# S5_Communications.net
KiCad netlist of a schematic drawn in Altium Designer
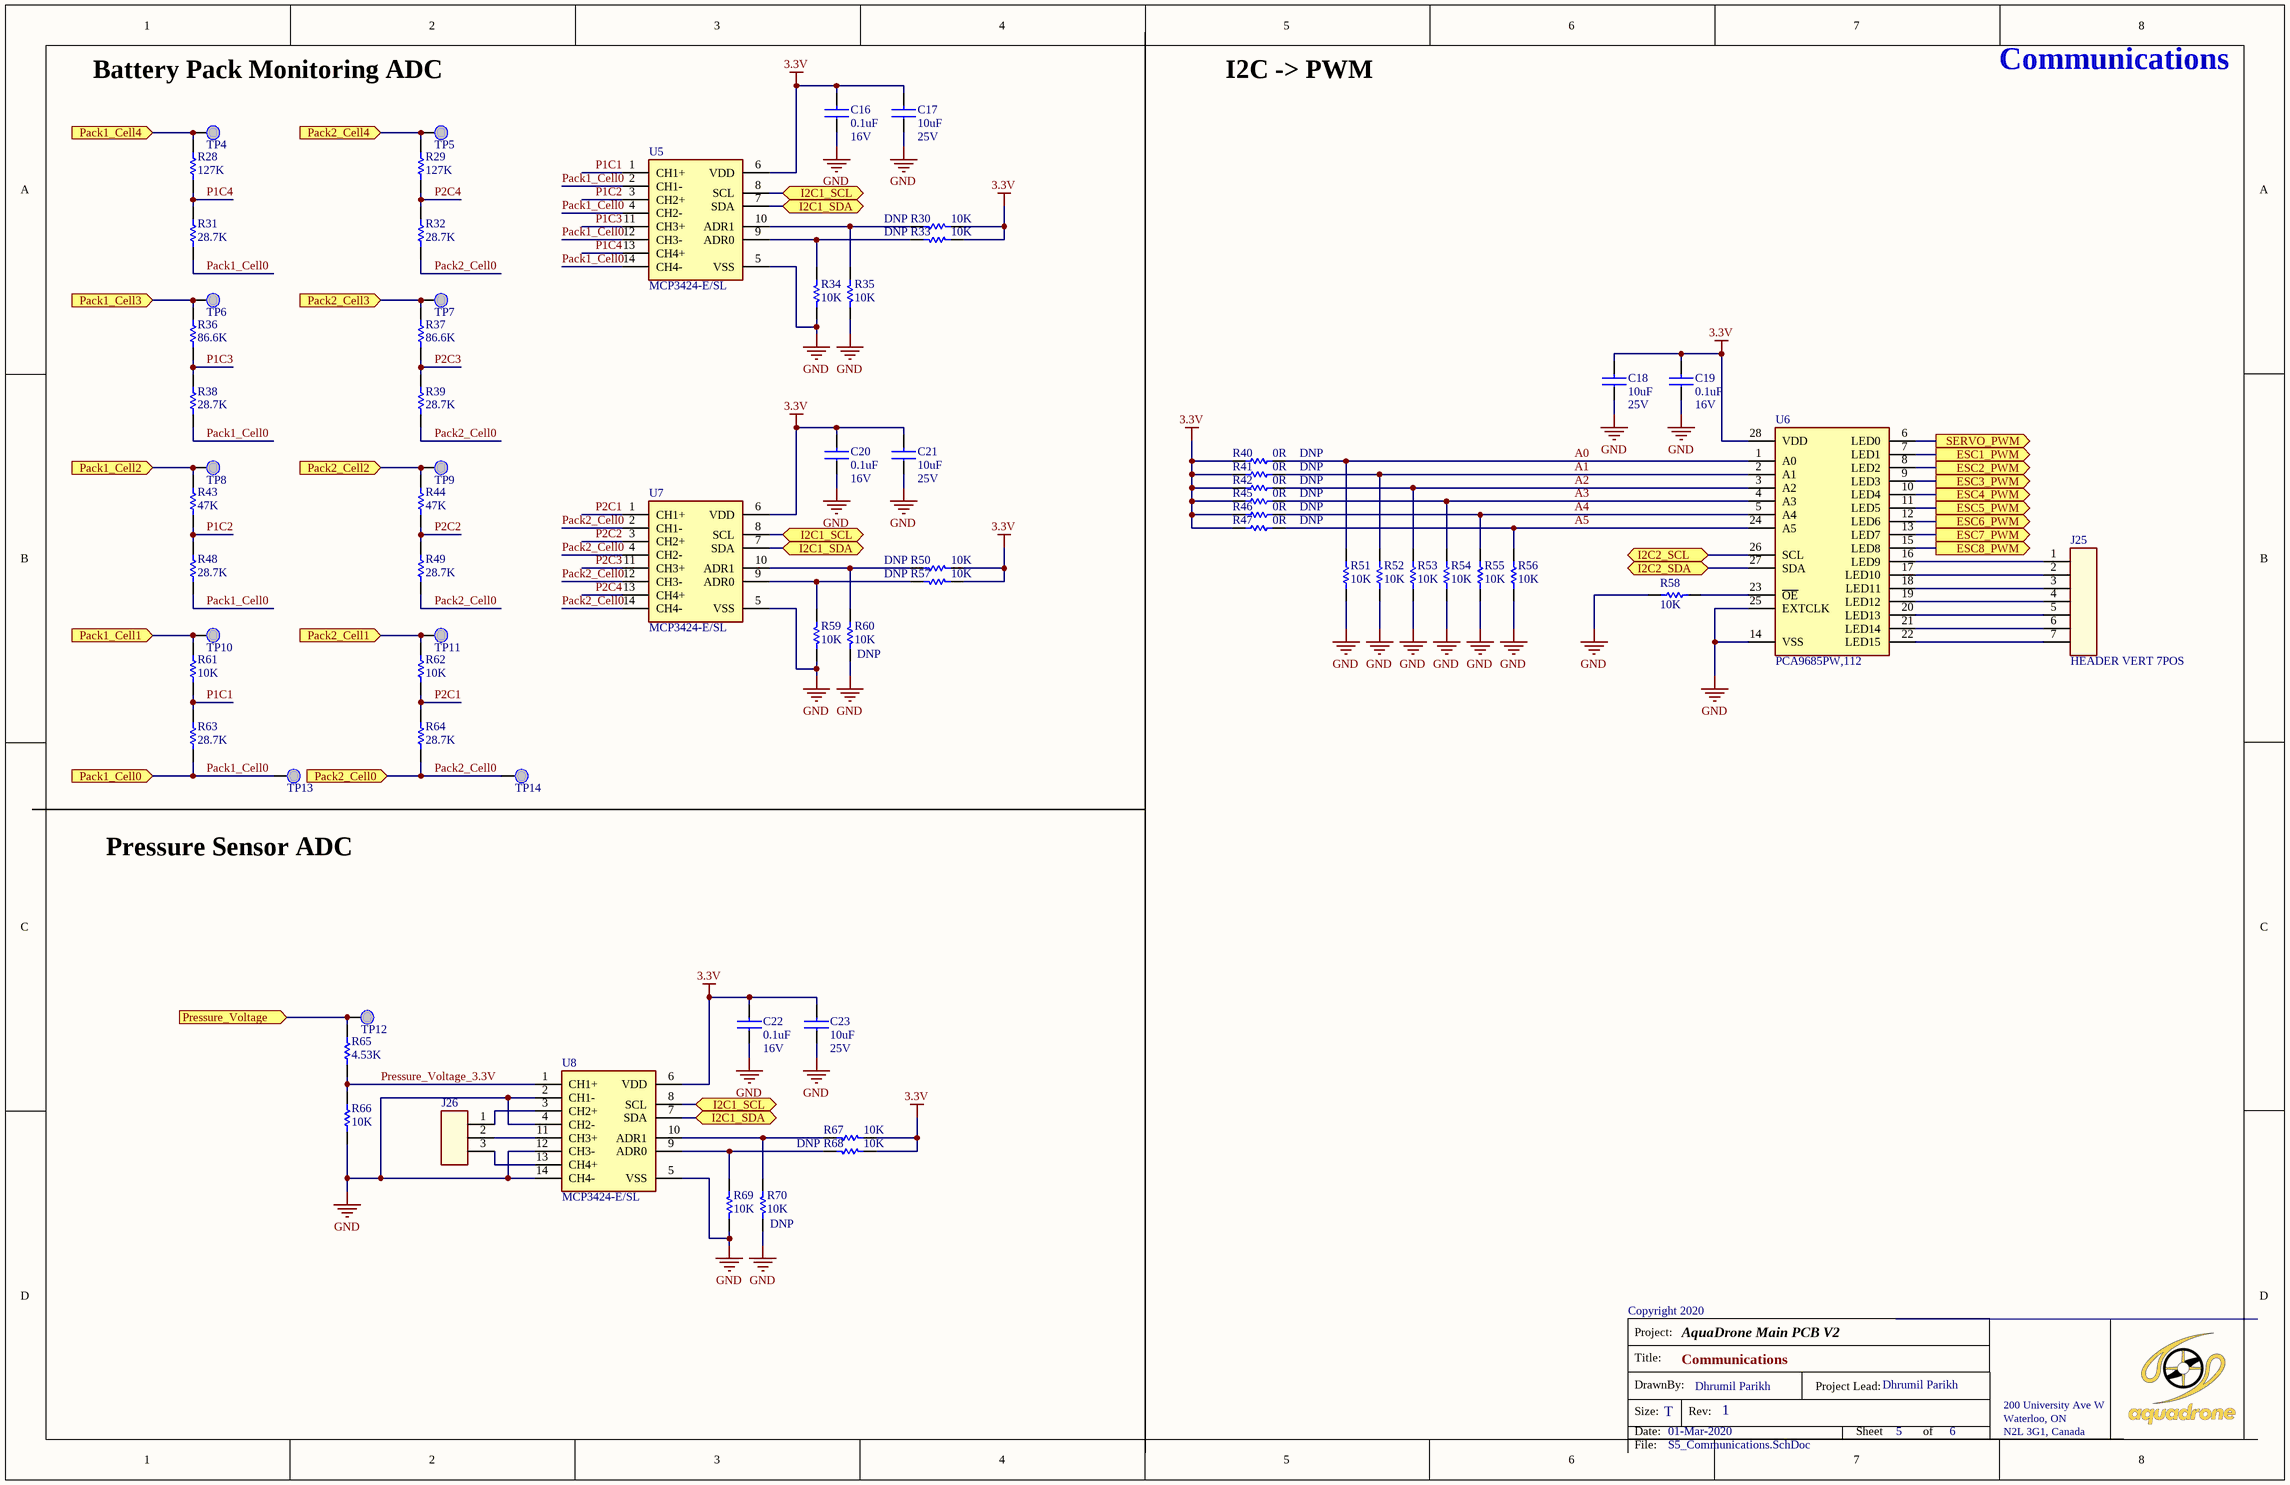
[diagram p0: S5_Communications.SchDoc]

(export (version "E")
  (design (tool "Eeschema 10.0.6"))
  (components
    (comp (ref "C16")
      (value "0.1uF")
      (footprint "RWMN:CAPC1608X09N")
      (description "CAP CER 0.1UF 16V X7R 0603")
      (fields
        (field (name "MFG") "KEMET")
        (field (name "MFG_PART_NO") "C0603C104M4RACTU")
        (field (name "VOLTAGE") "16V")
      )
      (libsource (lib "AquaDrone") (part "CAP CER 0.1UF 16V X7R 0603"))
    )
    (comp (ref "C17")
      (value "10uF")
      (footprint "RWMN:CAPC1608X09N")
      (description "CAP CER 10UF 25V X5R 0603")
      (fields
        (field (name "MFG") "KEMET")
        (field (name "MFG_PART_NO") "C1608X5R1E106M080AC")
        (field (name "VOLTAGE") "25V")
      )
      (libsource (lib "AquaDrone") (part "CAP CER 10UF 25V X5R 0603"))
    )
    (comp (ref "C18")
      (value "10uF")
      (footprint "RWMN:CAPC1608X09N")
      (description "CAP CER 10UF 25V X5R 0603")
      (fields
        (field (name "MFG") "KEMET")
        (field (name "MFG_PART_NO") "C1608X5R1E106M080AC")
        (field (name "VOLTAGE") "25V")
      )
      (libsource (lib "AquaDrone") (part "CAP CER 10UF 25V X5R 0603"))
    )
    (comp (ref "C19")
      (value "0.1uF")
      (footprint "RWMN:CAPC1608X09N")
      (description "CAP CER 0.1UF 16V X7R 0603")
      (fields
        (field (name "MFG") "KEMET")
        (field (name "MFG_PART_NO") "C0603C104M4RACTU")
        (field (name "VOLTAGE") "16V")
      )
      (libsource (lib "AquaDrone") (part "CAP CER 0.1UF 16V X7R 0603"))
    )
    (comp (ref "C20")
      (value "0.1uF")
      (footprint "RWMN:CAPC1608X09N")
      (description "CAP CER 0.1UF 16V X7R 0603")
      (fields
        (field (name "MFG") "KEMET")
        (field (name "MFG_PART_NO") "C0603C104M4RACTU")
        (field (name "VOLTAGE") "16V")
      )
      (libsource (lib "AquaDrone") (part "CAP CER 0.1UF 16V X7R 0603"))
    )
    (comp (ref "C21")
      (value "10uF")
      (footprint "RWMN:CAPC1608X09N")
      (description "CAP CER 10UF 25V X5R 0603")
      (fields
        (field (name "MFG") "KEMET")
        (field (name "MFG_PART_NO") "C1608X5R1E106M080AC")
        (field (name "VOLTAGE") "25V")
      )
      (libsource (lib "AquaDrone") (part "CAP CER 10UF 25V X5R 0603"))
    )
    (comp (ref "C22")
      (value "0.1uF")
      (footprint "RWMN:CAPC1608X09N")
      (description "CAP CER 0.1UF 16V X7R 0603")
      (fields
        (field (name "MFG") "KEMET")
        (field (name "MFG_PART_NO") "C0603C104M4RACTU")
        (field (name "VOLTAGE") "16V")
      )
      (libsource (lib "AquaDrone") (part "CAP CER 0.1UF 16V X7R 0603"))
    )
    (comp (ref "C23")
      (value "10uF")
      (footprint "RWMN:CAPC1608X09N")
      (description "CAP CER 10UF 25V X5R 0603")
      (fields
        (field (name "MFG") "KEMET")
        (field (name "MFG_PART_NO") "C1608X5R1E106M080AC")
        (field (name "VOLTAGE") "25V")
      )
      (libsource (lib "AquaDrone") (part "CAP CER 10UF 25V X5R 0603"))
    )
    (comp (ref "J25")
      (value "HEADER VERT 7POS")
      (footprint "61300711121")
      (description "CONN HEADER VERT 7POS 2.54MM")
      (fields (field (name "MFG") "Wurth Electronics Inc.") (field (name "MFG_PART_NO") "61300711121"))
      (libsource (lib "AquaDrone") (part "CONN HEADER VERT 7POS 2.54MM"))
    )
    (comp (ref "J26")
      (value "CONN HEADER VERT 3POS 2.54MM")
      (footprint "RWMN:61300311121")
      (fields (field (name "MFG") "Wurth Electronics Inc.") (field (name "MFG_PART_NO") "61300311121"))
      (libsource (lib "AquaDrone") (part "CONN HEADER VERT 3POS 2.54MM"))
    )
    (comp (ref "R28")
      (value "127K")
      (footprint "RESC1608X06N")
      (description "RES SMD 127K OHM 1% 1/10W 0603")
      (fields (field (name "MFG") "Vishay Dale") (field (name "MFG_PART_NO") "CRCW0603127KFKEA"))
      (libsource (lib "AquaDrone") (part "RES SMD 127K OHM 1% 1/10W 0603"))
    )
    (comp (ref "R29")
      (value "127K")
      (footprint "RESC1608X06N")
      (description "RES SMD 127K OHM 1% 1/10W 0603")
      (fields (field (name "MFG") "Vishay Dale") (field (name "MFG_PART_NO") "CRCW0603127KFKEA"))
      (libsource (lib "AquaDrone") (part "RES SMD 127K OHM 1% 1/10W 0603"))
    )
    (comp (ref "R30")
      (value "10K")
      (footprint "RESC1608X06N")
      (description "RES SMD 10K OHM 1% 1/10W 0603")
      (fields
        (field (name "MFG") "Vishay Dale")
        (field (name "NOSTUFF") "DNP")
        (field (name "MFG_PART_NO") "CRCW060310K0FKEA")
      )
      (libsource (lib "AquaDrone") (part "RES SMD 10K OHM 1% 1/10W 0603"))
    )
    (comp (ref "R31")
      (value "28.7K")
      (footprint "RESC1608X06N")
      (description "RES SMD 28.7K OHM 1% 1/10W 0603")
      (fields (field (name "MFG") "Yageo") (field (name "MFG_PART_NO") "RC0603FR-0728K7L"))
      (libsource (lib "AquaDrone") (part "RES SMD 28.7K OHM 1% 1/10W 0603"))
    )
    (comp (ref "R32")
      (value "28.7K")
      (footprint "RESC1608X06N")
      (description "RES SMD 28.7K OHM 1% 1/10W 0603")
      (fields (field (name "MFG") "Yageo") (field (name "MFG_PART_NO") "RC0603FR-0728K7L"))
      (libsource (lib "AquaDrone") (part "RES SMD 28.7K OHM 1% 1/10W 0603"))
    )
    (comp (ref "R33")
      (value "10K")
      (footprint "RESC1608X06N")
      (description "RES SMD 10K OHM 1% 1/10W 0603")
      (fields
        (field (name "MFG") "Vishay Dale")
        (field (name "NOSTUFF") "DNP")
        (field (name "MFG_PART_NO") "CRCW060310K0FKEA")
      )
      (libsource (lib "AquaDrone") (part "RES SMD 10K OHM 1% 1/10W 0603"))
    )
    (comp (ref "R34")
      (value "10K")
      (footprint "RESC1608X06N")
      (description "RES SMD 10K OHM 1% 1/10W 0603")
      (fields (field (name "MFG") "Vishay Dale") (field (name "MFG_PART_NO") "CRCW060310K0FKEA"))
      (libsource (lib "AquaDrone") (part "RES SMD 10K OHM 1% 1/10W 0603"))
    )
    (comp (ref "R35")
      (value "10K")
      (footprint "RESC1608X06N")
      (description "RES SMD 10K OHM 1% 1/10W 0603")
      (fields (field (name "MFG") "Vishay Dale") (field (name "MFG_PART_NO") "CRCW060310K0FKEA"))
      (libsource (lib "AquaDrone") (part "RES SMD 10K OHM 1% 1/10W 0603"))
    )
    (comp (ref "R36")
      (value "86.6K")
      (footprint "RESC1608X06N")
      (description "RES SMD 86.6K OHM 1% 1/10W 0603")
      (fields (field (name "MFG") "Yageo") (field (name "MFG_PART_NO") "RC0603FR-0786K6L"))
      (libsource (lib "AquaDrone") (part "RES SMD 86.6K OHM 1% 1/10W 0603"))
    )
    (comp (ref "R37")
      (value "86.6K")
      (footprint "RESC1608X06N")
      (description "RES SMD 86.6K OHM 1% 1/10W 0603")
      (fields (field (name "MFG") "Yageo") (field (name "MFG_PART_NO") "RC0603FR-0786K6L"))
      (libsource (lib "AquaDrone") (part "RES SMD 86.6K OHM 1% 1/10W 0603"))
    )
    (comp (ref "R38")
      (value "28.7K")
      (footprint "RESC1608X06N")
      (description "RES SMD 28.7K OHM 1% 1/10W 0603")
      (fields (field (name "MFG") "Yageo") (field (name "MFG_PART_NO") "RC0603FR-0728K7L"))
      (libsource (lib "AquaDrone") (part "RES SMD 28.7K OHM 1% 1/10W 0603"))
    )
    (comp (ref "R39")
      (value "28.7K")
      (footprint "RESC1608X06N")
      (description "RES SMD 28.7K OHM 1% 1/10W 0603")
      (fields (field (name "MFG") "Yageo") (field (name "MFG_PART_NO") "RC0603FR-0728K7L"))
      (libsource (lib "AquaDrone") (part "RES SMD 28.7K OHM 1% 1/10W 0603"))
    )
    (comp (ref "R40")
      (value "0R")
      (footprint "RESC2012X07N")
      (description "RES SMD 0 OHM JUMPER 1/8W 0805")
      (fields
        (field (name "MFG") "Panasonic")
        (field (name "NOSTUFF") "DNP")
        (field (name "MFG_PART_NO") "ERJ-6GEY0R00V")
      )
      (libsource (lib "AquaDrone") (part "RES SMD 0 OHM JUMPER 1/8W 0805"))
    )
    (comp (ref "R41")
      (value "0R")
      (footprint "RESC2012X07N")
      (description "RES SMD 0 OHM JUMPER 1/8W 0805")
      (fields
        (field (name "MFG") "Panasonic")
        (field (name "NOSTUFF") "DNP")
        (field (name "MFG_PART_NO") "ERJ-6GEY0R00V")
      )
      (libsource (lib "AquaDrone") (part "RES SMD 0 OHM JUMPER 1/8W 0805"))
    )
    (comp (ref "R42")
      (value "0R")
      (footprint "RESC2012X07N")
      (description "RES SMD 0 OHM JUMPER 1/8W 0805")
      (fields
        (field (name "MFG") "Panasonic")
        (field (name "NOSTUFF") "DNP")
        (field (name "MFG_PART_NO") "ERJ-6GEY0R00V")
      )
      (libsource (lib "AquaDrone") (part "RES SMD 0 OHM JUMPER 1/8W 0805"))
    )
    (comp (ref "R43")
      (value "47K")
      (footprint "RESC1608X06N")
      (description "RES SMD 47K OHM 1% 1/10W 0603")
      (fields (field (name "MFG") "Yageo") (field (name "MFG_PART_NO") "RC0603FR-0747KL"))
      (libsource (lib "AquaDrone") (part "RES SMD 47K OHM 1% 1/10W 0603"))
    )
    (comp (ref "R44")
      (value "47K")
      (footprint "RESC1608X06N")
      (description "RES SMD 47K OHM 1% 1/10W 0603")
      (fields (field (name "MFG") "Yageo") (field (name "MFG_PART_NO") "RC0603FR-0747KL"))
      (libsource (lib "AquaDrone") (part "RES SMD 47K OHM 1% 1/10W 0603"))
    )
    (comp (ref "R45")
      (value "0R")
      (footprint "RESC2012X07N")
      (description "RES SMD 0 OHM JUMPER 1/8W 0805")
      (fields
        (field (name "MFG") "Panasonic")
        (field (name "NOSTUFF") "DNP")
        (field (name "MFG_PART_NO") "ERJ-6GEY0R00V")
      )
      (libsource (lib "AquaDrone") (part "RES SMD 0 OHM JUMPER 1/8W 0805"))
    )
    (comp (ref "R46")
      (value "0R")
      (footprint "RESC2012X07N")
      (description "RES SMD 0 OHM JUMPER 1/8W 0805")
      (fields
        (field (name "MFG") "Panasonic")
        (field (name "NOSTUFF") "DNP")
        (field (name "MFG_PART_NO") "ERJ-6GEY0R00V")
      )
      (libsource (lib "AquaDrone") (part "RES SMD 0 OHM JUMPER 1/8W 0805"))
    )
    (comp (ref "R47")
      (value "0R")
      (footprint "RESC2012X07N")
      (description "RES SMD 0 OHM JUMPER 1/8W 0805")
      (fields
        (field (name "MFG") "Panasonic")
        (field (name "NOSTUFF") "DNP")
        (field (name "MFG_PART_NO") "ERJ-6GEY0R00V")
      )
      (libsource (lib "AquaDrone") (part "RES SMD 0 OHM JUMPER 1/8W 0805"))
    )
    (comp (ref "R48")
      (value "28.7K")
      (footprint "RESC1608X06N")
      (description "RES SMD 28.7K OHM 1% 1/10W 0603")
      (fields (field (name "MFG") "Yageo") (field (name "MFG_PART_NO") "RC0603FR-0728K7L"))
      (libsource (lib "AquaDrone") (part "RES SMD 28.7K OHM 1% 1/10W 0603"))
    )
    (comp (ref "R49")
      (value "28.7K")
      (footprint "RESC1608X06N")
      (description "RES SMD 28.7K OHM 1% 1/10W 0603")
      (fields (field (name "MFG") "Yageo") (field (name "MFG_PART_NO") "RC0603FR-0728K7L"))
      (libsource (lib "AquaDrone") (part "RES SMD 28.7K OHM 1% 1/10W 0603"))
    )
    (comp (ref "R50")
      (value "10K")
      (footprint "RESC1608X06N")
      (description "RES SMD 10K OHM 1% 1/10W 0603")
      (fields
        (field (name "MFG") "Vishay Dale")
        (field (name "NOSTUFF") "DNP")
        (field (name "MFG_PART_NO") "CRCW060310K0FKEA")
      )
      (libsource (lib "AquaDrone") (part "RES SMD 10K OHM 1% 1/10W 0603"))
    )
    (comp (ref "R51")
      (value "10K")
      (footprint "RESC1608X06N")
      (description "RES SMD 10K OHM 1% 1/10W 0603")
      (fields (field (name "MFG") "Vishay Dale") (field (name "MFG_PART_NO") "CRCW060310K0FKEA"))
      (libsource (lib "AquaDrone") (part "RES SMD 10K OHM 1% 1/10W 0603"))
    )
    (comp (ref "R52")
      (value "10K")
      (footprint "RESC1608X06N")
      (description "RES SMD 10K OHM 1% 1/10W 0603")
      (fields (field (name "MFG") "Vishay Dale") (field (name "MFG_PART_NO") "CRCW060310K0FKEA"))
      (libsource (lib "AquaDrone") (part "RES SMD 10K OHM 1% 1/10W 0603"))
    )
    (comp (ref "R53")
      (value "10K")
      (footprint "RESC1608X06N")
      (description "RES SMD 10K OHM 1% 1/10W 0603")
      (fields (field (name "MFG") "Vishay Dale") (field (name "MFG_PART_NO") "CRCW060310K0FKEA"))
      (libsource (lib "AquaDrone") (part "RES SMD 10K OHM 1% 1/10W 0603"))
    )
    (comp (ref "R54")
      (value "10K")
      (footprint "RESC1608X06N")
      (description "RES SMD 10K OHM 1% 1/10W 0603")
      (fields (field (name "MFG") "Vishay Dale") (field (name "MFG_PART_NO") "CRCW060310K0FKEA"))
      (libsource (lib "AquaDrone") (part "RES SMD 10K OHM 1% 1/10W 0603"))
    )
    (comp (ref "R55")
      (value "10K")
      (footprint "RESC1608X06N")
      (description "RES SMD 10K OHM 1% 1/10W 0603")
      (fields (field (name "MFG") "Vishay Dale") (field (name "MFG_PART_NO") "CRCW060310K0FKEA"))
      (libsource (lib "AquaDrone") (part "RES SMD 10K OHM 1% 1/10W 0603"))
    )
    (comp (ref "R56")
      (value "10K")
      (footprint "RESC1608X06N")
      (description "RES SMD 10K OHM 1% 1/10W 0603")
      (fields (field (name "MFG") "Vishay Dale") (field (name "MFG_PART_NO") "CRCW060310K0FKEA"))
      (libsource (lib "AquaDrone") (part "RES SMD 10K OHM 1% 1/10W 0603"))
    )
    (comp (ref "R57")
      (value "10K")
      (footprint "RESC1608X06N")
      (description "RES SMD 10K OHM 1% 1/10W 0603")
      (fields
        (field (name "MFG") "Vishay Dale")
        (field (name "NOSTUFF") "DNP")
        (field (name "MFG_PART_NO") "CRCW060310K0FKEA")
      )
      (libsource (lib "AquaDrone") (part "RES SMD 10K OHM 1% 1/10W 0603"))
    )
    (comp (ref "R58")
      (value "10K")
      (footprint "RESC1608X06N")
      (description "RES SMD 10K OHM 1% 1/10W 0603")
      (fields (field (name "MFG") "Vishay Dale") (field (name "MFG_PART_NO") "CRCW060310K0FKEA"))
      (libsource (lib "AquaDrone") (part "RES SMD 10K OHM 1% 1/10W 0603"))
    )
    (comp (ref "R59")
      (value "10K")
      (footprint "RESC1608X06N")
      (description "RES SMD 10K OHM 1% 1/10W 0603")
      (fields (field (name "MFG") "Vishay Dale") (field (name "MFG_PART_NO") "CRCW060310K0FKEA"))
      (libsource (lib "AquaDrone") (part "RES SMD 10K OHM 1% 1/10W 0603"))
    )
    (comp (ref "R60")
      (value "10K")
      (footprint "RESC1608X06N")
      (description "RES SMD 10K OHM 1% 1/10W 0603")
      (fields
        (field (name "MFG") "Vishay Dale")
        (field (name "NOSTUFF") "DNP")
        (field (name "MFG_PART_NO") "CRCW060310K0FKEA")
      )
      (libsource (lib "AquaDrone") (part "RES SMD 10K OHM 1% 1/10W 0603"))
    )
    (comp (ref "R61")
      (value "10K")
      (footprint "RESC1608X06N")
      (description "RES SMD 10K OHM 1% 1/10W 0603")
      (fields (field (name "MFG") "Vishay Dale") (field (name "MFG_PART_NO") "CRCW060310K0FKEA"))
      (libsource (lib "AquaDrone") (part "RES SMD 10K OHM 1% 1/10W 0603"))
    )
    (comp (ref "R62")
      (value "10K")
      (footprint "RESC1608X06N")
      (description "RES SMD 10K OHM 1% 1/10W 0603")
      (fields (field (name "MFG") "Vishay Dale") (field (name "MFG_PART_NO") "CRCW060310K0FKEA"))
      (libsource (lib "AquaDrone") (part "RES SMD 10K OHM 1% 1/10W 0603"))
    )
    (comp (ref "R63")
      (value "28.7K")
      (footprint "RESC1608X06N")
      (description "RES SMD 28.7K OHM 1% 1/10W 0603")
      (fields (field (name "MFG") "Yageo") (field (name "MFG_PART_NO") "RC0603FR-0728K7L"))
      (libsource (lib "AquaDrone") (part "RES SMD 28.7K OHM 1% 1/10W 0603"))
    )
    (comp (ref "R64")
      (value "28.7K")
      (footprint "RESC1608X06N")
      (description "RES SMD 28.7K OHM 1% 1/10W 0603")
      (fields (field (name "MFG") "Yageo") (field (name "MFG_PART_NO") "RC0603FR-0728K7L"))
      (libsource (lib "AquaDrone") (part "RES SMD 28.7K OHM 1% 1/10W 0603"))
    )
    (comp (ref "R65")
      (value "4.53K")
      (footprint "RESC1608X06N")
      (description "RES SMD 4.53K OHM 1% 1/10W 0603")
      (fields (field (name "MFG") "Yageo") (field (name "MFG_PART_NO") "RC0603FR-074K53L"))
      (libsource (lib "AquaDrone") (part "RES SMD 4.53K OHM 1% 1/10W 0603"))
    )
    (comp (ref "R66")
      (value "10K")
      (footprint "RESC1608X06N")
      (description "RES SMD 10K OHM 1% 1/10W 0603")
      (fields (field (name "MFG") "Vishay Dale") (field (name "MFG_PART_NO") "CRCW060310K0FKEA"))
      (libsource (lib "AquaDrone") (part "RES SMD 10K OHM 1% 1/10W 0603"))
    )
    (comp (ref "R67")
      (value "10K")
      (footprint "RESC1608X06N")
      (description "RES SMD 10K OHM 1% 1/10W 0603")
      (fields (field (name "MFG") "Vishay Dale") (field (name "MFG_PART_NO") "CRCW060310K0FKEA"))
      (libsource (lib "AquaDrone") (part "RES SMD 10K OHM 1% 1/10W 0603"))
    )
    (comp (ref "R68")
      (value "10K")
      (footprint "RESC1608X06N")
      (description "RES SMD 10K OHM 1% 1/10W 0603")
      (fields
        (field (name "MFG") "Vishay Dale")
        (field (name "NOSTUFF") "DNP")
        (field (name "MFG_PART_NO") "CRCW060310K0FKEA")
      )
      (libsource (lib "AquaDrone") (part "RES SMD 10K OHM 1% 1/10W 0603"))
    )
    (comp (ref "R69")
      (value "10K")
      (footprint "RESC1608X06N")
      (description "RES SMD 10K OHM 1% 1/10W 0603")
      (fields (field (name "MFG") "Vishay Dale") (field (name "MFG_PART_NO") "CRCW060310K0FKEA"))
      (libsource (lib "AquaDrone") (part "RES SMD 10K OHM 1% 1/10W 0603"))
    )
    (comp (ref "R70")
      (value "10K")
      (footprint "RESC1608X06N")
      (description "RES SMD 10K OHM 1% 1/10W 0603")
      (fields
        (field (name "MFG") "Vishay Dale")
        (field (name "NOSTUFF") "DNP")
        (field (name "MFG_PART_NO") "CRCW060310K0FKEA")
      )
      (libsource (lib "AquaDrone") (part "RES SMD 10K OHM 1% 1/10W 0603"))
    )
    (comp (ref "TP4")
      (value "Testpoint 1mm SMD Pad")
      (footprint "TP_SMD_1.0MM")
      (description "Testpoint 1.0mm SMD Pad")
      (libsource (lib "AquaDrone") (part "Testpoint 1mm SMD Pad"))
    )
    (comp (ref "TP5")
      (value "Testpoint 1mm SMD Pad")
      (footprint "TP_SMD_1.0MM")
      (description "Testpoint 1.0mm SMD Pad")
      (libsource (lib "AquaDrone") (part "Testpoint 1mm SMD Pad"))
    )
    (comp (ref "TP6")
      (value "Testpoint 1mm SMD Pad")
      (footprint "TP_SMD_1.0MM")
      (description "Testpoint 1.0mm SMD Pad")
      (libsource (lib "AquaDrone") (part "Testpoint 1mm SMD Pad"))
    )
    (comp (ref "TP7")
      (value "Testpoint 1mm SMD Pad")
      (footprint "TP_SMD_1.0MM")
      (description "Testpoint 1.0mm SMD Pad")
      (libsource (lib "AquaDrone") (part "Testpoint 1mm SMD Pad"))
    )
    (comp (ref "TP8")
      (value "Testpoint 1mm SMD Pad")
      (footprint "TP_SMD_1.0MM")
      (description "Testpoint 1.0mm SMD Pad")
      (libsource (lib "AquaDrone") (part "Testpoint 1mm SMD Pad"))
    )
    (comp (ref "TP9")
      (value "Testpoint 1mm SMD Pad")
      (footprint "TP_SMD_1.0MM")
      (description "Testpoint 1.0mm SMD Pad")
      (libsource (lib "AquaDrone") (part "Testpoint 1mm SMD Pad"))
    )
    (comp (ref "TP10")
      (value "Testpoint 1mm SMD Pad")
      (footprint "TP_SMD_1.0MM")
      (description "Testpoint 1.0mm SMD Pad")
      (libsource (lib "AquaDrone") (part "Testpoint 1mm SMD Pad"))
    )
    (comp (ref "TP11")
      (value "Testpoint 1mm SMD Pad")
      (footprint "TP_SMD_1.0MM")
      (description "Testpoint 1.0mm SMD Pad")
      (libsource (lib "AquaDrone") (part "Testpoint 1mm SMD Pad"))
    )
    (comp (ref "TP12")
      (value "Testpoint 1mm SMD Pad")
      (footprint "TP_SMD_1.0MM")
      (description "Testpoint 1.0mm SMD Pad")
      (libsource (lib "AquaDrone") (part "Testpoint 1mm SMD Pad"))
    )
    (comp (ref "TP13")
      (value "Testpoint 1mm SMD Pad")
      (footprint "TP_SMD_1.0MM")
      (description "Testpoint 1.0mm SMD Pad")
      (libsource (lib "AquaDrone") (part "Testpoint 1mm SMD Pad"))
    )
    (comp (ref "TP14")
      (value "Testpoint 1mm SMD Pad")
      (footprint "TP_SMD_1.0MM")
      (description "Testpoint 1.0mm SMD Pad")
      (libsource (lib "AquaDrone") (part "Testpoint 1mm SMD Pad"))
    )
    (comp (ref "U5")
      (value "IC ADC 18BIT SIGMA-DELTA 14SOIC")
      (footprint "SOIC127P600X175-14N")
      (fields (field (name "MFG") "Microchip Technology") (field (name "MFG_PART_NO") "MCP3424-E/SL"))
      (libsource (lib "AquaDrone") (part "IC ADC 18BIT SIGMA-DELTA 14SOIC"))
    )
    (comp (ref "U6")
      (value "IC LED DRVR LIN DIM 25MA 28TSSOP")
      (footprint "SOP65P640X110-28N")
      (fields (field (name "MFG") "NXP USA Inc.") (field (name "MFG_PART_NO") "PCA9685PW,112"))
      (libsource (lib "AquaDrone") (part "IC LED DRVR LIN DIM 25MA 28TSSOP"))
    )
    (comp (ref "U7")
      (value "IC ADC 18BIT SIGMA-DELTA 14SOIC")
      (footprint "SOIC127P600X175-14N")
      (fields (field (name "MFG") "Microchip Technology") (field (name "MFG_PART_NO") "MCP3424-E/SL"))
      (libsource (lib "AquaDrone") (part "IC ADC 18BIT SIGMA-DELTA 14SOIC"))
    )
    (comp (ref "U8")
      (value "IC ADC 18BIT SIGMA-DELTA 14SOIC")
      (footprint "SOIC127P600X175-14N")
      (fields (field (name "MFG") "Microchip Technology") (field (name "MFG_PART_NO") "MCP3424-E/SL"))
      (libsource (lib "AquaDrone") (part "IC ADC 18BIT SIGMA-DELTA 14SOIC"))
    )
  )
  (nets
    (net (code "1") (name "/A0") (class "Default")
      (node (ref "R40") (pin "2") (pinfunction "2_2") (pintype "passive"))
      (node (ref "R51") (pin "2") (pinfunction "2_2") (pintype "passive"))
      (node (ref "U6") (pin "1") (pinfunction "A0_1") (pintype "passive"))
    )
    (net (code "2") (name "/A1") (class "Default")
      (node (ref "R41") (pin "2") (pinfunction "2_2") (pintype "passive"))
      (node (ref "R52") (pin "2") (pinfunction "2_2") (pintype "passive"))
      (node (ref "U6") (pin "2") (pinfunction "A1_2") (pintype "passive"))
    )
    (net (code "3") (name "/A2") (class "Default")
      (node (ref "R42") (pin "2") (pinfunction "2_2") (pintype "passive"))
      (node (ref "R53") (pin "2") (pinfunction "2_2") (pintype "passive"))
      (node (ref "U6") (pin "3") (pinfunction "A2_3") (pintype "passive"))
    )
    (net (code "4") (name "/A3") (class "Default")
      (node (ref "R45") (pin "2") (pinfunction "2_2") (pintype "passive"))
      (node (ref "R54") (pin "2") (pinfunction "2_2") (pintype "passive"))
      (node (ref "U6") (pin "4") (pinfunction "A3_4") (pintype "passive"))
    )
    (net (code "5") (name "/A4") (class "Default")
      (node (ref "R46") (pin "2") (pinfunction "2_2") (pintype "passive"))
      (node (ref "R55") (pin "2") (pinfunction "2_2") (pintype "passive"))
      (node (ref "U6") (pin "5") (pinfunction "A4_5") (pintype "passive"))
    )
    (net (code "6") (name "/A5") (class "Default")
      (node (ref "R47") (pin "2") (pinfunction "2_2") (pintype "passive"))
      (node (ref "R56") (pin "2") (pinfunction "2_2") (pintype "passive"))
      (node (ref "U6") (pin "24") (pinfunction "A5_24") (pintype "passive"))
    )
    (net (code "7") (name "/ESC1_PWM") (class "Default")
      (node (ref "U6") (pin "7") (pinfunction "LED1_7") (pintype "passive"))
    )
    (net (code "8") (name "/ESC2_PWM") (class "Default")
      (node (ref "U6") (pin "8") (pinfunction "LED2_8") (pintype "passive"))
    )
    (net (code "9") (name "/ESC3_PWM") (class "Default")
      (node (ref "U6") (pin "9") (pinfunction "LED3_9") (pintype "passive"))
    )
    (net (code "10") (name "/ESC4_PWM") (class "Default")
      (node (ref "U6") (pin "10") (pinfunction "LED4_10") (pintype "passive"))
    )
    (net (code "11") (name "/ESC5_PWM") (class "Default")
      (node (ref "U6") (pin "11") (pinfunction "LED5_11") (pintype "passive"))
    )
    (net (code "12") (name "/ESC6_PWM") (class "Default")
      (node (ref "U6") (pin "12") (pinfunction "LED6_12") (pintype "passive"))
    )
    (net (code "13") (name "/ESC7_PWM") (class "Default")
      (node (ref "U6") (pin "13") (pinfunction "LED7_13") (pintype "passive"))
    )
    (net (code "14") (name "/ESC8_PWM") (class "Default")
      (node (ref "U6") (pin "15") (pinfunction "LED8_15") (pintype "passive"))
    )
    (net (code "15") (name "/I2C1_SCL") (class "Default")
      (node (ref "U5") (pin "8") (pinfunction "SCL_8") (pintype "passive"))
      (node (ref "U7") (pin "8") (pinfunction "SCL_8") (pintype "passive"))
      (node (ref "U8") (pin "8") (pinfunction "SCL_8") (pintype "passive"))
    )
    (net (code "16") (name "/I2C1_SDA") (class "Default")
      (node (ref "U5") (pin "7") (pinfunction "SDA_7") (pintype "passive"))
      (node (ref "U7") (pin "7") (pinfunction "SDA_7") (pintype "passive"))
      (node (ref "U8") (pin "7") (pinfunction "SDA_7") (pintype "passive"))
    )
    (net (code "17") (name "/I2C2_SCL") (class "Default")
      (node (ref "U6") (pin "26") (pinfunction "SCL_26") (pintype "passive"))
    )
    (net (code "18") (name "/I2C2_SDA") (class "Default")
      (node (ref "U6") (pin "27") (pinfunction "SDA_27") (pintype "passive"))
    )
    (net (code "19") (name "/P1C1") (class "Default")
      (node (ref "R61") (pin "1") (pinfunction "1_1") (pintype "passive"))
      (node (ref "R63") (pin "2") (pinfunction "2_2") (pintype "passive"))
      (node (ref "U5") (pin "1") (pinfunction "CH1+_1") (pintype "passive"))
    )
    (net (code "20") (name "/P1C2") (class "Default")
      (node (ref "R43") (pin "1") (pinfunction "1_1") (pintype "passive"))
      (node (ref "R48") (pin "2") (pinfunction "2_2") (pintype "passive"))
      (node (ref "U5") (pin "3") (pinfunction "CH2+_3") (pintype "passive"))
    )
    (net (code "21") (name "/P1C3") (class "Default")
      (node (ref "R36") (pin "1") (pinfunction "1_1") (pintype "passive"))
      (node (ref "R38") (pin "2") (pinfunction "2_2") (pintype "passive"))
      (node (ref "U5") (pin "11") (pinfunction "CH3+_11") (pintype "passive"))
    )
    (net (code "22") (name "/P1C4") (class "Default")
      (node (ref "R28") (pin "1") (pinfunction "1_1") (pintype "passive"))
      (node (ref "R31") (pin "2") (pinfunction "2_2") (pintype "passive"))
      (node (ref "U5") (pin "13") (pinfunction "CH4+_13") (pintype "passive"))
    )
    (net (code "23") (name "/P2C1") (class "Default")
      (node (ref "R62") (pin "1") (pinfunction "1_1") (pintype "passive"))
      (node (ref "R64") (pin "2") (pinfunction "2_2") (pintype "passive"))
      (node (ref "U7") (pin "1") (pinfunction "CH1+_1") (pintype "passive"))
    )
    (net (code "24") (name "/P2C2") (class "Default")
      (node (ref "R44") (pin "1") (pinfunction "1_1") (pintype "passive"))
      (node (ref "R49") (pin "2") (pinfunction "2_2") (pintype "passive"))
      (node (ref "U7") (pin "3") (pinfunction "CH2+_3") (pintype "passive"))
    )
    (net (code "25") (name "/P2C3") (class "Default")
      (node (ref "R37") (pin "1") (pinfunction "1_1") (pintype "passive"))
      (node (ref "R39") (pin "2") (pinfunction "2_2") (pintype "passive"))
      (node (ref "U7") (pin "11") (pinfunction "CH3+_11") (pintype "passive"))
    )
    (net (code "26") (name "/P2C4") (class "Default")
      (node (ref "R29") (pin "1") (pinfunction "1_1") (pintype "passive"))
      (node (ref "R32") (pin "2") (pinfunction "2_2") (pintype "passive"))
      (node (ref "U7") (pin "13") (pinfunction "CH4+_13") (pintype "passive"))
    )
    (net (code "27") (name "/Pack1_Cell0") (class "Default")
      (node (ref "R31") (pin "1") (pinfunction "1_1") (pintype "passive"))
      (node (ref "R38") (pin "1") (pinfunction "1_1") (pintype "passive"))
      (node (ref "R48") (pin "1") (pinfunction "1_1") (pintype "passive"))
      (node (ref "R63") (pin "1") (pinfunction "1_1") (pintype "passive"))
      (node (ref "TP13") (pin "1") (pinfunction "1_1") (pintype "passive"))
      (node (ref "U5") (pin "12") (pinfunction "CH3-_12") (pintype "passive"))
      (node (ref "U5") (pin "14") (pinfunction "CH4-_14") (pintype "passive"))
      (node (ref "U5") (pin "2") (pinfunction "CH1-_2") (pintype "passive"))
      (node (ref "U5") (pin "4") (pinfunction "CH2-_4") (pintype "passive"))
    )
    (net (code "28") (name "/Pack1_Cell1") (class "Default")
      (node (ref "R61") (pin "2") (pinfunction "2_2") (pintype "passive"))
      (node (ref "TP10") (pin "1") (pinfunction "1_1") (pintype "passive"))
    )
    (net (code "29") (name "/Pack1_Cell2") (class "Default")
      (node (ref "R43") (pin "2") (pinfunction "2_2") (pintype "passive"))
      (node (ref "TP8") (pin "1") (pinfunction "1_1") (pintype "passive"))
    )
    (net (code "30") (name "/Pack1_Cell3") (class "Default")
      (node (ref "R36") (pin "2") (pinfunction "2_2") (pintype "passive"))
      (node (ref "TP6") (pin "1") (pinfunction "1_1") (pintype "passive"))
    )
    (net (code "31") (name "/Pack1_Cell4") (class "Default")
      (node (ref "R28") (pin "2") (pinfunction "2_2") (pintype "passive"))
      (node (ref "TP4") (pin "1") (pinfunction "1_1") (pintype "passive"))
    )
    (net (code "32") (name "/Pack2_Cell0") (class "Default")
      (node (ref "R32") (pin "1") (pinfunction "1_1") (pintype "passive"))
      (node (ref "R39") (pin "1") (pinfunction "1_1") (pintype "passive"))
      (node (ref "R49") (pin "1") (pinfunction "1_1") (pintype "passive"))
      (node (ref "R64") (pin "1") (pinfunction "1_1") (pintype "passive"))
      (node (ref "TP14") (pin "1") (pinfunction "1_1") (pintype "passive"))
      (node (ref "U7") (pin "12") (pinfunction "CH3-_12") (pintype "passive"))
      (node (ref "U7") (pin "14") (pinfunction "CH4-_14") (pintype "passive"))
      (node (ref "U7") (pin "2") (pinfunction "CH1-_2") (pintype "passive"))
      (node (ref "U7") (pin "4") (pinfunction "CH2-_4") (pintype "passive"))
    )
    (net (code "33") (name "/Pack2_Cell1") (class "Default")
      (node (ref "R62") (pin "2") (pinfunction "2_2") (pintype "passive"))
      (node (ref "TP11") (pin "1") (pinfunction "1_1") (pintype "passive"))
    )
    (net (code "34") (name "/Pack2_Cell2") (class "Default")
      (node (ref "R44") (pin "2") (pinfunction "2_2") (pintype "passive"))
      (node (ref "TP9") (pin "1") (pinfunction "1_1") (pintype "passive"))
    )
    (net (code "35") (name "/Pack2_Cell3") (class "Default")
      (node (ref "R37") (pin "2") (pinfunction "2_2") (pintype "passive"))
      (node (ref "TP7") (pin "1") (pinfunction "1_1") (pintype "passive"))
    )
    (net (code "36") (name "/Pack2_Cell4") (class "Default")
      (node (ref "R29") (pin "2") (pinfunction "2_2") (pintype "passive"))
      (node (ref "TP5") (pin "1") (pinfunction "1_1") (pintype "passive"))
    )
    (net (code "37") (name "/Pressure_Voltage") (class "Default")
      (node (ref "R65") (pin "2") (pinfunction "2_2") (pintype "passive"))
      (node (ref "TP12") (pin "1") (pinfunction "1_1") (pintype "passive"))
    )
    (net (code "38") (name "/Pressure_Voltage_3.3V") (class "Default")
      (node (ref "R65") (pin "1") (pinfunction "1_1") (pintype "passive"))
      (node (ref "R66") (pin "2") (pinfunction "2_2") (pintype "passive"))
      (node (ref "U8") (pin "1") (pinfunction "CH1+_1") (pintype "passive"))
    )
    (net (code "39") (name "/SERVO_PWM") (class "Default")
      (node (ref "U6") (pin "6") (pinfunction "LED0_6") (pintype "passive"))
    )
    (net (code "40") (name "3.3V") (class "Default")
      (node (ref "C16") (pin "2") (pinfunction "2_2") (pintype "passive"))
      (node (ref "C17") (pin "2") (pinfunction "2_2") (pintype "passive"))
      (node (ref "C18") (pin "2") (pinfunction "2_2") (pintype "passive"))
      (node (ref "C19") (pin "2") (pinfunction "2_2") (pintype "passive"))
      (node (ref "C20") (pin "2") (pinfunction "2_2") (pintype "passive"))
      (node (ref "C21") (pin "2") (pinfunction "2_2") (pintype "passive"))
      (node (ref "C22") (pin "2") (pinfunction "2_2") (pintype "passive"))
      (node (ref "C23") (pin "2") (pinfunction "2_2") (pintype "passive"))
      (node (ref "R30") (pin "1") (pinfunction "1_1") (pintype "passive"))
      (node (ref "R33") (pin "1") (pinfunction "1_1") (pintype "passive"))
      (node (ref "R40") (pin "1") (pinfunction "1_1") (pintype "passive"))
      (node (ref "R41") (pin "1") (pinfunction "1_1") (pintype "passive"))
      (node (ref "R42") (pin "1") (pinfunction "1_1") (pintype "passive"))
      (node (ref "R45") (pin "1") (pinfunction "1_1") (pintype "passive"))
      (node (ref "R46") (pin "1") (pinfunction "1_1") (pintype "passive"))
      (node (ref "R47") (pin "1") (pinfunction "1_1") (pintype "passive"))
      (node (ref "R50") (pin "1") (pinfunction "1_1") (pintype "passive"))
      (node (ref "R57") (pin "1") (pinfunction "1_1") (pintype "passive"))
      (node (ref "R67") (pin "1") (pinfunction "1_1") (pintype "passive"))
      (node (ref "R68") (pin "1") (pinfunction "1_1") (pintype "passive"))
      (node (ref "U5") (pin "6") (pinfunction "VDD_6") (pintype "power_in"))
      (node (ref "U6") (pin "28") (pinfunction "VDD_28") (pintype "passive"))
      (node (ref "U7") (pin "6") (pinfunction "VDD_6") (pintype "power_in"))
      (node (ref "U8") (pin "6") (pinfunction "VDD_6") (pintype "power_in"))
    )
    (net (code "41") (name "GND") (class "Default")
      (node (ref "C16") (pin "1") (pinfunction "1_1") (pintype "passive"))
      (node (ref "C17") (pin "1") (pinfunction "1_1") (pintype "passive"))
      (node (ref "C18") (pin "1") (pinfunction "1_1") (pintype "passive"))
      (node (ref "C19") (pin "1") (pinfunction "1_1") (pintype "passive"))
      (node (ref "C20") (pin "1") (pinfunction "1_1") (pintype "passive"))
      (node (ref "C21") (pin "1") (pinfunction "1_1") (pintype "passive"))
      (node (ref "C22") (pin "1") (pinfunction "1_1") (pintype "passive"))
      (node (ref "C23") (pin "1") (pinfunction "1_1") (pintype "passive"))
      (node (ref "R34") (pin "1") (pinfunction "1_1") (pintype "passive"))
      (node (ref "R35") (pin "1") (pinfunction "1_1") (pintype "passive"))
      (node (ref "R51") (pin "1") (pinfunction "1_1") (pintype "passive"))
      (node (ref "R52") (pin "1") (pinfunction "1_1") (pintype "passive"))
      (node (ref "R53") (pin "1") (pinfunction "1_1") (pintype "passive"))
      (node (ref "R54") (pin "1") (pinfunction "1_1") (pintype "passive"))
      (node (ref "R55") (pin "1") (pinfunction "1_1") (pintype "passive"))
      (node (ref "R56") (pin "1") (pinfunction "1_1") (pintype "passive"))
      (node (ref "R58") (pin "1") (pinfunction "1_1") (pintype "passive"))
      (node (ref "R59") (pin "1") (pinfunction "1_1") (pintype "passive"))
      (node (ref "R60") (pin "1") (pinfunction "1_1") (pintype "passive"))
      (node (ref "R66") (pin "1") (pinfunction "1_1") (pintype "passive"))
      (node (ref "R69") (pin "1") (pinfunction "1_1") (pintype "passive"))
      (node (ref "R70") (pin "1") (pinfunction "1_1") (pintype "passive"))
      (node (ref "U5") (pin "5") (pinfunction "VSS_5") (pintype "power_in"))
      (node (ref "U6") (pin "14") (pinfunction "VSS_14") (pintype "passive"))
      (node (ref "U6") (pin "25") (pinfunction "EXTCLK_25") (pintype "passive"))
      (node (ref "U7") (pin "5") (pinfunction "VSS_5") (pintype "power_in"))
      (node (ref "U8") (pin "12") (pinfunction "CH3-_12") (pintype "passive"))
      (node (ref "U8") (pin "14") (pinfunction "CH4-_14") (pintype "passive"))
      (node (ref "U8") (pin "2") (pinfunction "CH1-_2") (pintype "passive"))
      (node (ref "U8") (pin "4") (pinfunction "CH2-_4") (pintype "passive"))
      (node (ref "U8") (pin "5") (pinfunction "VSS_5") (pintype "power_in"))
    )
    (net (code "42") (name "Net-(U5-ADR0)") (class "Default")
      (node (ref "R33") (pin "2") (pinfunction "2_2") (pintype "passive"))
      (node (ref "R34") (pin "2") (pinfunction "2_2") (pintype "passive"))
      (node (ref "U5") (pin "9") (pinfunction "ADR0_9") (pintype "passive"))
    )
    (net (code "43") (name "Net-(U5-ADR1)") (class "Default")
      (node (ref "R30") (pin "2") (pinfunction "2_2") (pintype "passive"))
      (node (ref "R35") (pin "2") (pinfunction "2_2") (pintype "passive"))
      (node (ref "U5") (pin "10") (pinfunction "ADR1_10") (pintype "passive"))
    )
    (net (code "44") (name "Net-(U6-LED9)") (class "Default")
      (node (ref "J25") (pin "1") (pintype "passive"))
      (node (ref "U6") (pin "16") (pinfunction "LED9_16") (pintype "passive"))
    )
    (net (code "45") (name "Net-(U6-LED10)") (class "Default")
      (node (ref "J25") (pin "2") (pintype "passive"))
      (node (ref "U6") (pin "17") (pinfunction "LED10_17") (pintype "passive"))
    )
    (net (code "46") (name "Net-(U6-LED11)") (class "Default")
      (node (ref "J25") (pin "3") (pintype "passive"))
      (node (ref "U6") (pin "18") (pinfunction "LED11_18") (pintype "passive"))
    )
    (net (code "47") (name "Net-(U6-LED12)") (class "Default")
      (node (ref "J25") (pin "4") (pintype "passive"))
      (node (ref "U6") (pin "19") (pinfunction "LED12_19") (pintype "passive"))
    )
    (net (code "48") (name "Net-(U6-LED13)") (class "Default")
      (node (ref "J25") (pin "5") (pintype "passive"))
      (node (ref "U6") (pin "20") (pinfunction "LED13_20") (pintype "passive"))
    )
    (net (code "49") (name "Net-(U6-LED14)") (class "Default")
      (node (ref "J25") (pin "6") (pintype "passive"))
      (node (ref "U6") (pin "21") (pinfunction "LED14_21") (pintype "passive"))
    )
    (net (code "50") (name "Net-(U6-LED15)") (class "Default")
      (node (ref "J25") (pin "7") (pintype "passive"))
      (node (ref "U6") (pin "22") (pinfunction "LED15_22") (pintype "passive"))
    )
    (net (code "51") (name "Net-(U6-~{OE})") (class "Default")
      (node (ref "R58") (pin "2") (pinfunction "2_2") (pintype "passive"))
      (node (ref "U6") (pin "23") (pinfunction "~{OE}_23") (pintype "passive"))
    )
    (net (code "52") (name "Net-(U7-ADR0)") (class "Default")
      (node (ref "R57") (pin "2") (pinfunction "2_2") (pintype "passive"))
      (node (ref "R59") (pin "2") (pinfunction "2_2") (pintype "passive"))
      (node (ref "U7") (pin "9") (pinfunction "ADR0_9") (pintype "passive"))
    )
    (net (code "53") (name "Net-(U7-ADR1)") (class "Default")
      (node (ref "R50") (pin "2") (pinfunction "2_2") (pintype "passive"))
      (node (ref "R60") (pin "2") (pinfunction "2_2") (pintype "passive"))
      (node (ref "U7") (pin "10") (pinfunction "ADR1_10") (pintype "passive"))
    )
    (net (code "54") (name "Net-(U8-ADR0)") (class "Default")
      (node (ref "R68") (pin "2") (pinfunction "2_2") (pintype "passive"))
      (node (ref "R69") (pin "2") (pinfunction "2_2") (pintype "passive"))
      (node (ref "U8") (pin "9") (pinfunction "ADR0_9") (pintype "passive"))
    )
    (net (code "55") (name "Net-(U8-ADR1)") (class "Default")
      (node (ref "R67") (pin "2") (pinfunction "2_2") (pintype "passive"))
      (node (ref "R70") (pin "2") (pinfunction "2_2") (pintype "passive"))
      (node (ref "U8") (pin "10") (pinfunction "ADR1_10") (pintype "passive"))
    )
    (net (code "56") (name "Net-(U8-CH2+)") (class "Default")
      (node (ref "J26") (pin "1") (pintype "passive"))
      (node (ref "U8") (pin "3") (pinfunction "CH2+_3") (pintype "passive"))
    )
    (net (code "57") (name "Net-(U8-CH3+)") (class "Default")
      (node (ref "J26") (pin "2") (pintype "passive"))
      (node (ref "U8") (pin "11") (pinfunction "CH3+_11") (pintype "passive"))
    )
    (net (code "58") (name "Net-(U8-CH4+)") (class "Default")
      (node (ref "J26") (pin "3") (pintype "passive"))
      (node (ref "U8") (pin "13") (pinfunction "CH4+_13") (pintype "passive"))
    )
  )
)
